# Regulators.net
KiCad netlist of a schematic drawn in Altium Designer
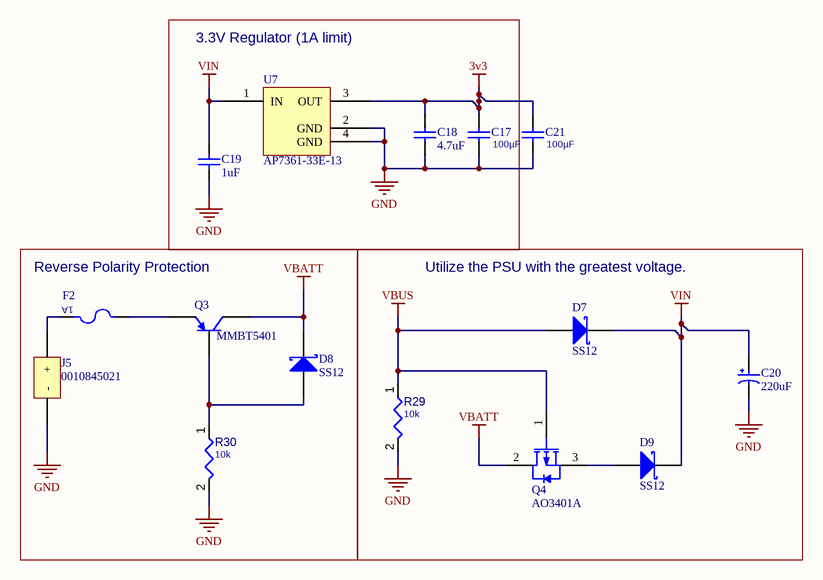
[diagram p0: Regulators.SchDoc]

(export (version "E")
  (design (tool "Eeschema 10.0.6"))
  (components
    (comp (ref "C17")
      (value "100µF")
      (footprint "Capacitor_1206")
      (description "Ceramic Capacitor 100uF 6.3V X5R 1206")
      (fields (field (name "JLCPCB PART #") "C15008") (field (name "Comment") "CL31A107MQHNNNE"))
      (libsource (lib "RIT Launch Initiative") (part "CAPACITOR"))
    )
    (comp (ref "C18")
      (value "GRM155R60J475ME87D")
      (footprint "Capacitor_0402")
      (description "6.3V 4.7uF X5R ±20% 0402 Multilayer Ceramic Capacitors MLCC - SMD/SMT ROHS")
      (fields (field (name "CAPACITANCE") "4.7uF") (field (name "TOLERANCE") "20%"))
      (libsource (lib "RIT Launch Initiative") (part "CAPACITOR"))
    )
    (comp (ref "C19")
      (value "GRM155R61E105KA12D")
      (footprint "Capacitor_0402")
      (description "Chip Capacitor 1uF - 0402 25 V ±10% Tolerance X5R Multilayer Ceramic Chip Capacitor")
      (fields
        (field (name "CAPACITANCE") "1uF")
        (field (name "TOLERANCE") "10%")
        (field (name "JLCPCB PART #") "C52923")
      )
      (libsource (lib "RIT Launch Initiative") (part "CAPACITOR"))
    )
    (comp (ref "C20")
      (value "T491D227K010AT")
      (footprint "CASE-D_7343")
      (description "Cap Tant Solid 220uF 10V D CASE 10% (7.3 X 4.3 X 2.8mm) SMD 7343-31 0.5 Ohm 125 C T/R")
      (fields
        (field (name "CAPACITANCE") "220uF")
        (field (name "TOLERANCE") "10%")
        (field (name "JLCPCB PART #") "C116577")
      )
      (libsource (lib "RIT Launch Initiative") (part "CAPACITOR POLARIZED"))
    )
    (comp (ref "C21")
      (value "100µF")
      (footprint "Capacitor_1206")
      (description "Ceramic Capacitor 100uF 6.3V X5R 1206")
      (fields (field (name "Comment") "CL31A107MQHNNNE"))
      (libsource (lib "RIT Launch Initiative") (part "CAPACITOR"))
    )
    (comp (ref "D7")
      (value "SS12")
      (footprint "FAIR-DO-214AC-2_V")
      (description "Schottky Rectifier, 20 V, 1 A, -65 to 125 degC, 2-Pin DO-214AC, RoHS, Tape and Reel")
      (fields (field (name "MANUFACTURER") "Fairchild") (field (name "JLCPCB PART #") "C353243"))
      (libsource (lib "RIT Launch Initiative") (part "DSKY-AK-2"))
    )
    (comp (ref "D8")
      (value "SS12")
      (footprint "FAIR-DO-214AC-2_V")
      (description "Schottky Rectifier, 20 V, 1 A, -65 to 125 degC, 2-Pin DO-214AC, RoHS, Tape and Reel")
      (fields (field (name "MANUFACTURER") "Fairchild"))
      (libsource (lib "RIT Launch Initiative") (part "DSKY-AK-2"))
    )
    (comp (ref "D9")
      (value "SS12")
      (footprint "FAIR-DO-214AC-2_V")
      (description "Schottky Rectifier, 20 V, 1 A, -65 to 125 degC, 2-Pin DO-214AC, RoHS, Tape and Reel")
      (fields (field (name "MANUFACTURER") "Fairchild"))
      (libsource (lib "RIT Launch Initiative") (part "DSKY-AK-2"))
    )
    (comp (ref "F2")
      (value "0466001.NRHF")
      (footprint "FP-0466-MFG")
      (description "Fuse Chip Very Fast Acting 1A 63V SMD Solder Pad 1206 T/R CSA")
      (libsource (lib "RIT Launch Initiative") (part "FUSE"))
    )
    (comp (ref "J5")
      (value "0010845021")
      (footprint "0010845021-Footprint-1")
      (description "Header Connector, pcb Mount, plug, 2 Contacts, skt, 0.25 Pitch, pc Tail Terminal, polarized Lck")
      (libsource (lib "RIT Launch Initiative") (part "0010845021"))
    )
    (comp (ref "Q3")
      (value "MMBT5401")
      (footprint "SOT223127P600-8N")
      (description "Bipolar Transistor, PNP, 150V, 300mW, SOT-23, 150V, 600mA")
      (fields (field (name "JLCPCB PART #") "C8326"))
      (libsource (lib "RIT Launch Initiative") (part "MMBT5401-Symbol"))
    )
    (comp (ref "Q4")
      (value "AO3401A")
      (footprint "AO-SOT-23-3L_V")
      (description "Trans Mosfet P-ch 30V 4A 3-PIN SOT-23 T/r")
      (fields (field (name "JLCPCB PART #") "C15127"))
      (libsource (lib "RIT Launch Initiative") (part "PEMOS-GSD-3"))
    )
    (comp (ref "R29")
      (value "10k")
      (footprint "RESC0402(1005)_L")
      (description "Chip Resistor, 10 kOhms, +/-1 %, 63 mW, -55 to 125 degC, 0402")
      (fields (field (name "POWER") "63mW") (field (name "TOLERANCE") "1%"))
      (libsource (lib "RIT Launch Initiative") (part "RES-2"))
    )
    (comp (ref "R30")
      (value "10k")
      (footprint "RESC0402(1005)_L")
      (description "Chip Resistor, 10 kOhms, +/-1 %, 63 mW, -55 to 125 degC, 0402")
      (fields (field (name "POWER") "63mW") (field (name "TOLERANCE") "1%"))
      (libsource (lib "RIT Launch Initiative") (part "RES-2"))
    )
    (comp (ref "U7")
      (value "AP7361-33E-13")
      (footprint "AP7361-33E-13-Footprint-1")
      (description "AP7361 Series 3.3 V 1 A Low SMT Dropout Fixed-Mode Regulator - SOT-223")
      (libsource (lib "RIT Launch Initiative") (part "AP7361-33E-13-Symbol-1"))
    )
  )
  (nets
    (net (code "1") (name "3v3") (class "Default")
      (node (ref "C17") (pin "2") (pinfunction "2_2") (pintype "passive"))
      (node (ref "C18") (pin "2") (pinfunction "2_2") (pintype "passive"))
      (node (ref "C21") (pin "2") (pinfunction "2_2") (pintype "passive"))
      (node (ref "U7") (pin "3") (pinfunction "OUT_3") (pintype "passive"))
    )
    (net (code "2") (name "GND") (class "Default")
      (node (ref "C17") (pin "1") (pinfunction "1_1") (pintype "passive"))
      (node (ref "C18") (pin "1") (pinfunction "1_1") (pintype "passive"))
      (node (ref "C19") (pin "1") (pinfunction "1_1") (pintype "passive"))
      (node (ref "C20") (pin "2") (pinfunction "2_2") (pintype "passive"))
      (node (ref "C21") (pin "1") (pinfunction "1_1") (pintype "passive"))
      (node (ref "J5") (pin "2") (pinfunction "-_2") (pintype "passive"))
      (node (ref "R29") (pin "2") (pinfunction "2_2") (pintype "passive"))
      (node (ref "R30") (pin "2") (pinfunction "2_2") (pintype "passive"))
      (node (ref "U7") (pin "2") (pinfunction "GND_2") (pintype "passive"))
      (node (ref "U7") (pin "4") (pinfunction "GND_4") (pintype "passive"))
    )
    (net (code "3") (name "Net-(D8-A)") (class "Default")
      (node (ref "D8") (pin "1") (pinfunction "A_1") (pintype "passive"))
      (node (ref "Q3") (pin "1") (pinfunction "B_1") (pintype "passive"))
      (node (ref "R30") (pin "1") (pinfunction "1_1") (pintype "passive"))
    )
    (net (code "4") (name "Net-(D9-A)") (class "Default")
      (node (ref "D9") (pin "1") (pinfunction "A_1") (pintype "passive"))
      (node (ref "Q4") (pin "3") (pinfunction "DRAIN_3") (pintype "passive"))
    )
    (net (code "5") (name "Net-(J5-+)") (class "Default")
      (node (ref "F2") (pin "2") (pinfunction "2_2") (pintype "passive"))
      (node (ref "J5") (pin "1") (pinfunction "+_1") (pintype "passive"))
    )
    (net (code "6") (name "Net-(Q3-E)") (class "Default")
      (node (ref "F2") (pin "1") (pinfunction "1_1") (pintype "passive"))
      (node (ref "Q3") (pin "2") (pinfunction "E_2") (pintype "passive"))
    )
    (net (code "7") (name "VBATT") (class "Default")
      (node (ref "D8") (pin "2") (pinfunction "K_2") (pintype "passive"))
      (node (ref "Q3") (pin "3") (pinfunction "C_3") (pintype "passive"))
      (node (ref "Q4") (pin "2") (pinfunction "SOURCE_2") (pintype "passive"))
    )
    (net (code "8") (name "VBUS") (class "Default")
      (node (ref "D7") (pin "1") (pinfunction "A_1") (pintype "passive"))
      (node (ref "Q4") (pin "1") (pinfunction "GATE_1") (pintype "passive"))
      (node (ref "R29") (pin "1") (pinfunction "1_1") (pintype "passive"))
    )
    (net (code "9") (name "VIN") (class "Default")
      (node (ref "C19") (pin "2") (pinfunction "2_2") (pintype "passive"))
      (node (ref "C20") (pin "1") (pinfunction "1_1") (pintype "passive"))
      (node (ref "D7") (pin "2") (pinfunction "K_2") (pintype "passive"))
      (node (ref "D9") (pin "2") (pinfunction "K_2") (pintype "passive"))
      (node (ref "U7") (pin "1") (pinfunction "IN_1") (pintype "passive"))
    )
  )
)
